# mainboard_motor_v1_5.net
KiCad netlist of a schematic drawn in Altium Designer
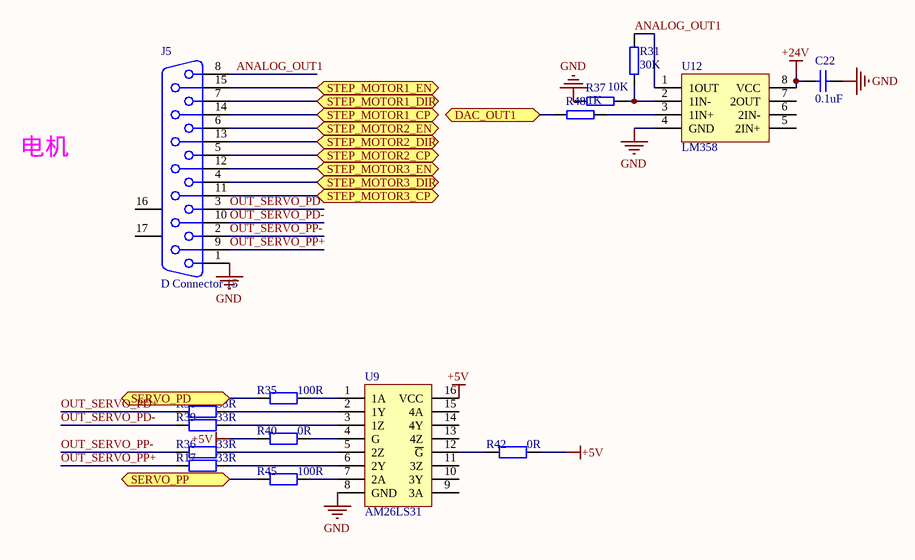
[diagram p0: mainboard_motor.v1.5.SchDoc]

(export (version "E")
  (design (tool "Eeschema 10.0.6"))
  (components
    (comp (ref "C22")
      (value "0.1uF")
      (footprint "0805")
      (description "Capacitor")
      (fields (field (name "PUBLISHER") "Altium Limited"))
      (libsource (lib "TIAN's Schlib") (part "Cap"))
    )
    (comp (ref "J5")
      (value "D Connector 15")
      (footprint "DSUB1.385-2H15")
      (description "Receptacle Assembly, 15 Position, Right Angle")
      (fields (field (name "PUBLISHER") "Altium Limited"))
      (libsource (lib "Miscellaneous Connectors") (part "D Connector 15"))
    )
    (comp (ref "R17")
      (value "33R")
      (footprint "0805")
      (description "Resistor")
      (fields (field (name "PUBLISHER") "Altium Limited"))
      (libsource (lib "TIAN's Schlib") (part "Res2"))
    )
    (comp (ref "R31")
      (value "30K")
      (footprint "0805")
      (description "电阻")
      (libsource (lib "Component") (part "RES"))
    )
    (comp (ref "R35")
      (value "100R")
      (footprint "0805")
      (description "Resistor")
      (fields (field (name "PUBLISHER") "Altium Limited"))
      (libsource (lib "TIAN's Schlib") (part "Res2"))
    )
    (comp (ref "R36")
      (value "33R")
      (footprint "0805")
      (description "Resistor")
      (fields (field (name "PUBLISHER") "Altium Limited"))
      (libsource (lib "TIAN's Schlib") (part "Res2"))
    )
    (comp (ref "R37")
      (value "10K")
      (footprint "0805")
      (description "电阻")
      (libsource (lib "Component") (part "RES"))
    )
    (comp (ref "R38")
      (value "33R")
      (footprint "0805")
      (description "Resistor")
      (fields (field (name "PUBLISHER") "Altium Limited"))
      (libsource (lib "TIAN's Schlib") (part "Res2"))
    )
    (comp (ref "R39")
      (value "33R")
      (footprint "0805")
      (description "Resistor")
      (fields (field (name "PUBLISHER") "Altium Limited"))
      (libsource (lib "TIAN's Schlib") (part "Res2"))
    )
    (comp (ref "R40")
      (value "0R")
      (footprint "0805")
      (description "Resistor")
      (fields (field (name "PUBLISHER") "Altium Limited"))
      (libsource (lib "TIAN's Schlib") (part "Res2"))
    )
    (comp (ref "R42")
      (value "0R")
      (footprint "0805")
      (description "Resistor")
      (fields (field (name "PUBLISHER") "Altium Limited"))
      (libsource (lib "TIAN's Schlib") (part "Res2"))
    )
    (comp (ref "R45")
      (value "100R")
      (footprint "0805")
      (description "Resistor")
      (fields (field (name "PUBLISHER") "Altium Limited"))
      (libsource (lib "TIAN's Schlib") (part "Res2"))
    )
    (comp (ref "R48")
      (value "1K")
      (footprint "0805")
      (description "电阻")
      (libsource (lib "Component") (part "RES"))
    )
    (comp (ref "U9") (value "AM26LS31") (footprint "SO-16") (libsource (lib "Chip") (part "AM26LS31")))
    (comp (ref "U12") (value "LM358") (footprint "SO-8") (libsource (lib "Chip") (part "LM358")))
  )
  (nets
    (net (code "1") (name "+5V") (class "Default")
      (node (ref "R40") (pin "2") (pinfunction "2_2") (pintype "passive"))
      (node (ref "R42") (pin "1") (pinfunction "1_1") (pintype "passive"))
      (node (ref "U9") (pin "16") (pinfunction "VCC_16") (pintype "passive"))
    )
    (net (code "2") (name "+24V") (class "Default")
      (node (ref "C22") (pin "2") (pinfunction "2_2") (pintype "passive"))
      (node (ref "U12") (pin "8") (pinfunction "VCC_8") (pintype "passive"))
    )
    (net (code "3") (name "/ANALOG_OUT1") (class "Default")
      (node (ref "J5") (pin "8") (pinfunction "8_8") (pintype "passive"))
      (node (ref "R31") (pin "1") (pinfunction "1_1") (pintype "passive"))
      (node (ref "U12") (pin "1") (pinfunction "1OUT_1") (pintype "passive"))
    )
    (net (code "4") (name "/DAC_OUT1") (class "Default")
      (node (ref "R48") (pin "2") (pinfunction "2_2") (pintype "passive"))
    )
    (net (code "5") (name "/OUT_SERVO_PD+") (class "Default")
      (node (ref "J5") (pin "3") (pinfunction "3_3") (pintype "passive"))
      (node (ref "R38") (pin "2") (pinfunction "2_2") (pintype "passive"))
    )
    (net (code "6") (name "/OUT_SERVO_PD-") (class "Default")
      (node (ref "J5") (pin "10") (pinfunction "10_10") (pintype "passive"))
      (node (ref "R39") (pin "2") (pinfunction "2_2") (pintype "passive"))
    )
    (net (code "7") (name "/OUT_SERVO_PP+") (class "Default")
      (node (ref "J5") (pin "9") (pinfunction "9_9") (pintype "passive"))
      (node (ref "R17") (pin "2") (pinfunction "2_2") (pintype "passive"))
    )
    (net (code "8") (name "/OUT_SERVO_PP-") (class "Default")
      (node (ref "J5") (pin "2") (pinfunction "2_2") (pintype "passive"))
      (node (ref "R36") (pin "2") (pinfunction "2_2") (pintype "passive"))
    )
    (net (code "9") (name "/SERVO_PD") (class "Default")
      (node (ref "R35") (pin "2") (pinfunction "2_2") (pintype "passive"))
    )
    (net (code "10") (name "/SERVO_PP") (class "Default")
      (node (ref "R45") (pin "2") (pinfunction "2_2") (pintype "passive"))
    )
    (net (code "11") (name "/STEP_MOTOR1_CP") (class "Default")
      (node (ref "J5") (pin "14") (pinfunction "14_14") (pintype "passive"))
    )
    (net (code "12") (name "/STEP_MOTOR1_DIR") (class "Default")
      (node (ref "J5") (pin "7") (pinfunction "7_7") (pintype "passive"))
    )
    (net (code "13") (name "/STEP_MOTOR1_EN") (class "Default")
      (node (ref "J5") (pin "15") (pinfunction "15_15") (pintype "passive"))
    )
    (net (code "14") (name "/STEP_MOTOR2_CP") (class "Default")
      (node (ref "J5") (pin "5") (pinfunction "5_5") (pintype "passive"))
    )
    (net (code "15") (name "/STEP_MOTOR2_DIR") (class "Default")
      (node (ref "J5") (pin "13") (pinfunction "13_13") (pintype "passive"))
    )
    (net (code "16") (name "/STEP_MOTOR2_EN") (class "Default")
      (node (ref "J5") (pin "6") (pinfunction "6_6") (pintype "passive"))
    )
    (net (code "17") (name "/STEP_MOTOR3_CP") (class "Default")
      (node (ref "J5") (pin "11") (pinfunction "11_11") (pintype "passive"))
    )
    (net (code "18") (name "/STEP_MOTOR3_DIR") (class "Default")
      (node (ref "J5") (pin "4") (pinfunction "4_4") (pintype "passive"))
    )
    (net (code "19") (name "/STEP_MOTOR3_EN") (class "Default")
      (node (ref "J5") (pin "12") (pinfunction "12_12") (pintype "passive"))
    )
    (net (code "20") (name "GND") (class "Default")
      (node (ref "C22") (pin "1") (pinfunction "1_1") (pintype "passive"))
      (node (ref "J5") (pin "1") (pinfunction "1_1") (pintype "passive"))
      (node (ref "R37") (pin "2") (pinfunction "2_2") (pintype "passive"))
      (node (ref "U12") (pin "4") (pinfunction "GND_4") (pintype "passive"))
      (node (ref "U9") (pin "8") (pinfunction "GND_8") (pintype "passive"))
    )
    (net (code "21") (name "Net-(U9-1A)") (class "Default")
      (node (ref "R35") (pin "1") (pinfunction "1_1") (pintype "passive"))
      (node (ref "U9") (pin "1") (pinfunction "1A_1") (pintype "passive"))
    )
    (net (code "22") (name "Net-(U9-1Y)") (class "Default")
      (node (ref "R38") (pin "1") (pinfunction "1_1") (pintype "passive"))
      (node (ref "U9") (pin "2") (pinfunction "1Y_2") (pintype "passive"))
    )
    (net (code "23") (name "Net-(U9-1Z)") (class "Default")
      (node (ref "R39") (pin "1") (pinfunction "1_1") (pintype "passive"))
      (node (ref "U9") (pin "3") (pinfunction "1Z_3") (pintype "passive"))
    )
    (net (code "24") (name "Net-(U9-2A)") (class "Default")
      (node (ref "R45") (pin "1") (pinfunction "1_1") (pintype "passive"))
      (node (ref "U9") (pin "7") (pinfunction "2A_7") (pintype "passive"))
    )
    (net (code "25") (name "Net-(U9-2Y)") (class "Default")
      (node (ref "R17") (pin "1") (pinfunction "1_1") (pintype "passive"))
      (node (ref "U9") (pin "6") (pinfunction "2Y_6") (pintype "passive"))
    )
    (net (code "26") (name "Net-(U9-2Z)") (class "Default")
      (node (ref "R36") (pin "1") (pinfunction "1_1") (pintype "passive"))
      (node (ref "U9") (pin "5") (pinfunction "2Z_5") (pintype "passive"))
    )
    (net (code "27") (name "Net-(U9-G)") (class "Default")
      (node (ref "R40") (pin "1") (pinfunction "1_1") (pintype "passive"))
      (node (ref "U9") (pin "4") (pinfunction "G_4") (pintype "passive"))
    )
    (net (code "28") (name "Net-(U9-~{G})") (class "Default")
      (node (ref "R42") (pin "2") (pinfunction "2_2") (pintype "passive"))
      (node (ref "U9") (pin "12") (pinfunction "~{G}_12") (pintype "passive"))
    )
    (net (code "29") (name "Net-(U12-1IN+)") (class "Default")
      (node (ref "R48") (pin "1") (pinfunction "1_1") (pintype "passive"))
      (node (ref "U12") (pin "3") (pinfunction "1IN+_3") (pintype "passive"))
    )
    (net (code "30") (name "Net-(U12-1IN-)") (class "Default")
      (node (ref "R31") (pin "2") (pinfunction "2_2") (pintype "passive"))
      (node (ref "R37") (pin "1") (pinfunction "1_1") (pintype "passive"))
      (node (ref "U12") (pin "2") (pinfunction "1IN-_2") (pintype "passive"))
    )
    (net (code "31") (name "unconnected-(J5-MH1-Pad16)") (class "Default")
      (node (ref "J5") (pin "16") (pinfunction "MH1_16") (pintype "passive"))
    )
    (net (code "32") (name "unconnected-(J5-MH2-Pad17)") (class "Default")
      (node (ref "J5") (pin "17") (pinfunction "MH2_17") (pintype "passive"))
    )
    (net (code "33") (name "unconnected-(U9-3A-Pad9)") (class "Default")
      (node (ref "U9") (pin "9") (pinfunction "3A_9") (pintype "passive"))
    )
    (net (code "34") (name "unconnected-(U9-3Y-Pad10)") (class "Default")
      (node (ref "U9") (pin "10") (pinfunction "3Y_10") (pintype "passive"))
    )
    (net (code "35") (name "unconnected-(U9-3Z-Pad11)") (class "Default")
      (node (ref "U9") (pin "11") (pinfunction "3Z_11") (pintype "passive"))
    )
    (net (code "36") (name "unconnected-(U9-4A-Pad15)") (class "Default")
      (node (ref "U9") (pin "15") (pinfunction "4A_15") (pintype "passive"))
    )
    (net (code "37") (name "unconnected-(U9-4Y-Pad14)") (class "Default")
      (node (ref "U9") (pin "14") (pinfunction "4Y_14") (pintype "passive"))
    )
    (net (code "38") (name "unconnected-(U9-4Z-Pad13)") (class "Default")
      (node (ref "U9") (pin "13") (pinfunction "4Z_13") (pintype "passive"))
    )
    (net (code "39") (name "unconnected-(U12-2IN+-Pad5)") (class "Default")
      (node (ref "U12") (pin "5") (pinfunction "2IN+_5") (pintype "passive"))
    )
    (net (code "40") (name "unconnected-(U12-2IN--Pad6)") (class "Default")
      (node (ref "U12") (pin "6") (pinfunction "2IN-_6") (pintype "passive"))
    )
    (net (code "41") (name "unconnected-(U12-2OUT-Pad7)") (class "Default")
      (node (ref "U12") (pin "7") (pinfunction "2OUT_7") (pintype "passive"))
    )
  )
)
